# nRF51x22_qfaa.net
KiCad netlist of a schematic drawn in EAGLE
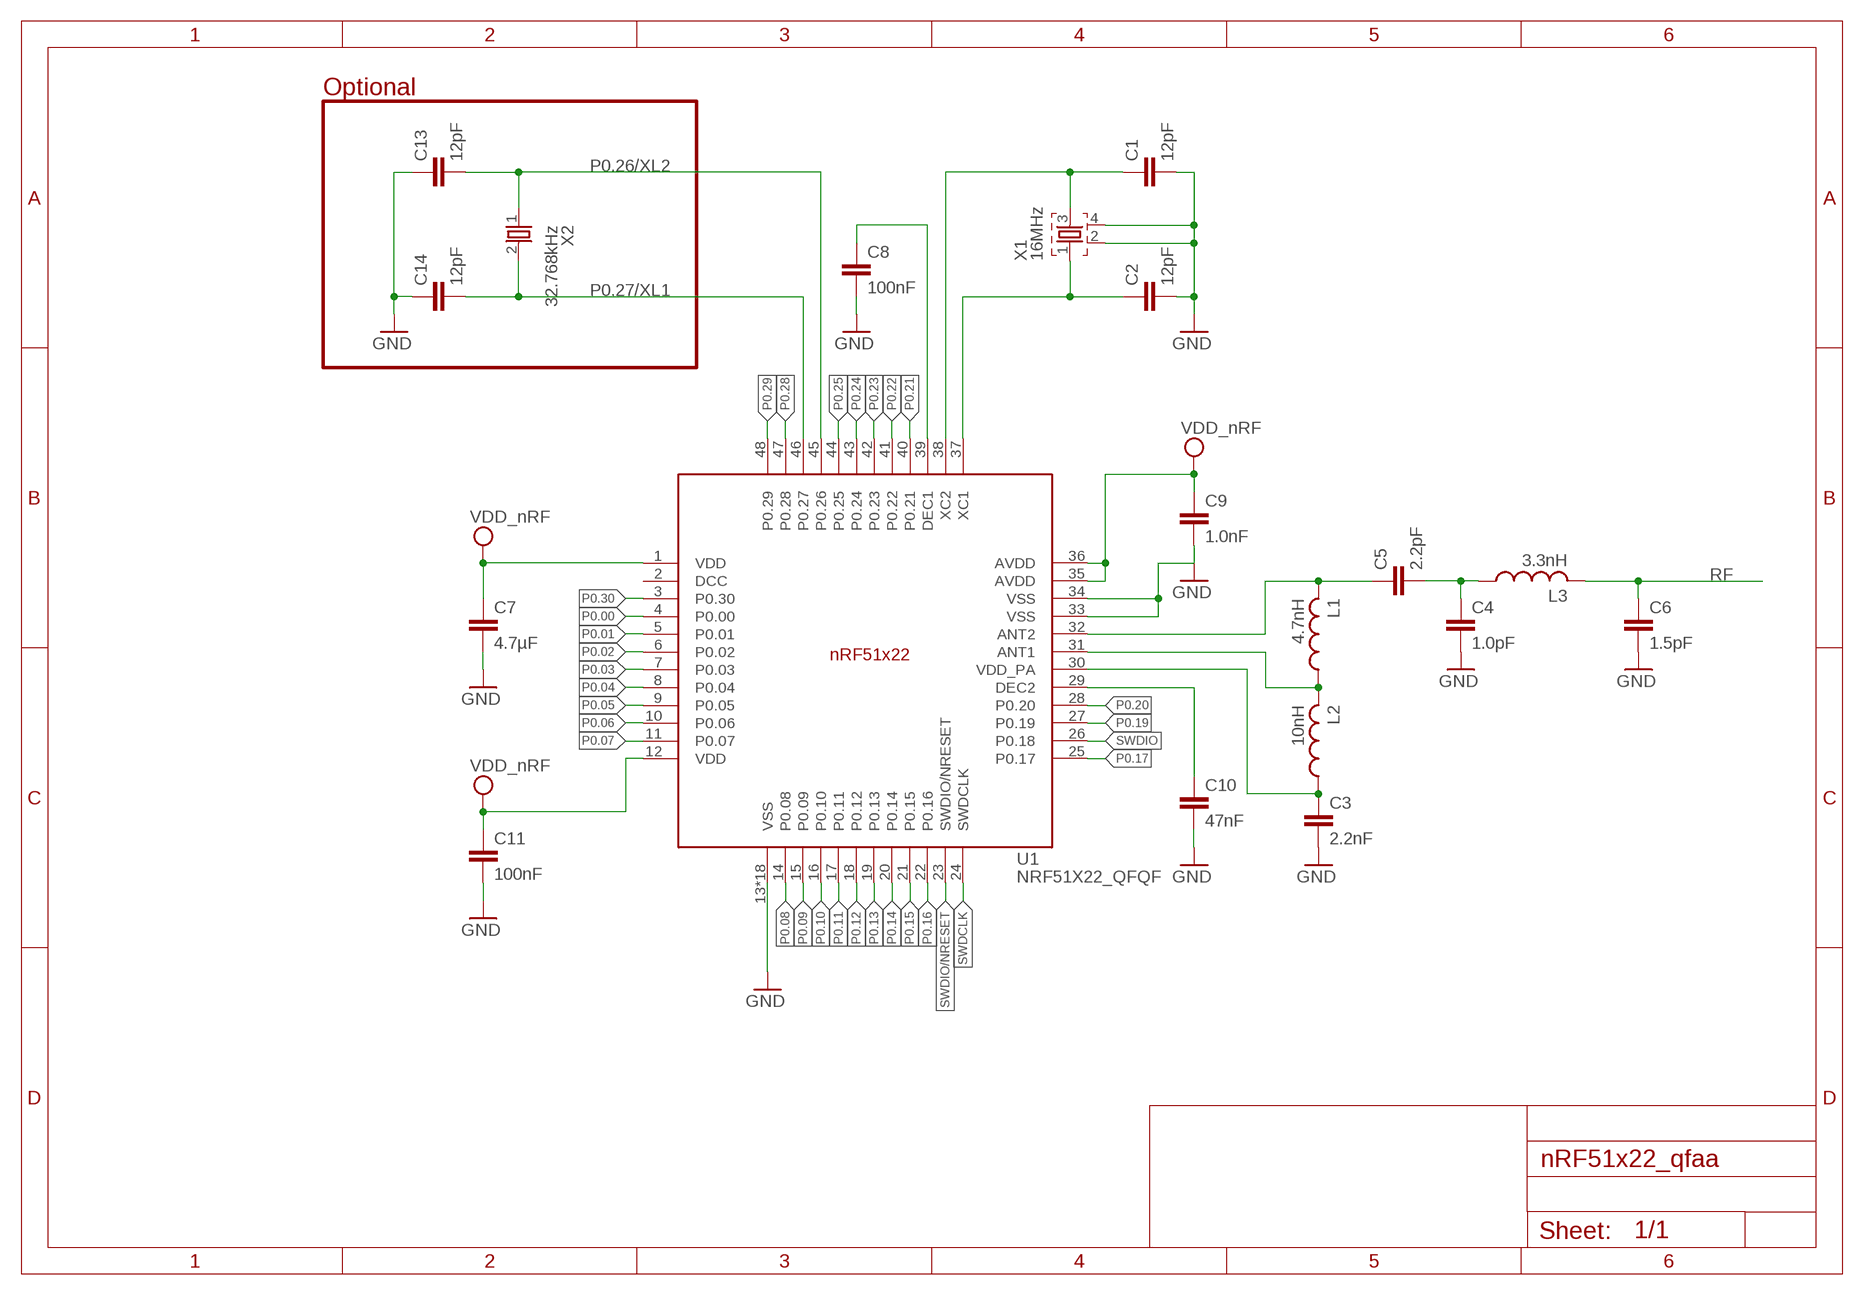
[diagram p0: schematic, sheet 1]

(export (version "E")
  (design (tool "Eeschema 10.0.6"))
  (components
    (comp (ref "C1")
      (value "12pF")
      (footprint "eagle-import:RESC0402_N")
      (libsource (lib "eagle-import") (part "CAPACITOR_0402_N"))
    )
    (comp (ref "C2")
      (value "12pF")
      (footprint "eagle-import:RESC0402_N")
      (libsource (lib "eagle-import") (part "CAPACITOR_0402_N"))
    )
    (comp (ref "C3")
      (value "2.2nF")
      (footprint "eagle-import:RESC0402_N")
      (libsource (lib "eagle-import") (part "CAPACITOR_0402_N"))
    )
    (comp (ref "C4")
      (value "1.0pF")
      (footprint "eagle-import:RESC0402_N")
      (libsource (lib "eagle-import") (part "CAPACITOR_0402_N"))
    )
    (comp (ref "C5")
      (value "2.2pF")
      (footprint "eagle-import:RESC0402_N")
      (libsource (lib "eagle-import") (part "CAPACITOR_0402_N"))
    )
    (comp (ref "C6")
      (value "1.5pF")
      (footprint "eagle-import:RESC0402_N")
      (libsource (lib "eagle-import") (part "CAPACITOR_0402_N"))
    )
    (comp (ref "C7")
      (value "4.7µF")
      (footprint "eagle-import:RESC0603_N")
      (libsource (lib "eagle-import") (part "CAPACITOR_0603_N"))
    )
    (comp (ref "C8")
      (value "100nF")
      (footprint "eagle-import:RESC0402_N")
      (libsource (lib "eagle-import") (part "CAPACITOR_0402_N"))
    )
    (comp (ref "C9")
      (value "1.0nF")
      (footprint "eagle-import:RESC0402_N")
      (libsource (lib "eagle-import") (part "CAPACITOR_0402_N"))
    )
    (comp (ref "C10")
      (value "47nF")
      (footprint "eagle-import:RESC0402_N")
      (libsource (lib "eagle-import") (part "CAPACITOR_0402_N"))
    )
    (comp (ref "C11")
      (value "100nF")
      (footprint "eagle-import:RESC0402_N")
      (libsource (lib "eagle-import") (part "CAPACITOR_0402_N"))
    )
    (comp (ref "C13")
      (value "12pF")
      (footprint "eagle-import:RESC0402_N")
      (libsource (lib "eagle-import") (part "CAPACITOR_0402_N"))
    )
    (comp (ref "C14")
      (value "12pF")
      (footprint "eagle-import:RESC0402_N")
      (libsource (lib "eagle-import") (part "CAPACITOR_0402_N"))
    )
    (comp (ref "L1")
      (value "4.7nH")
      (footprint "eagle-import:RESC0402_N")
      (libsource (lib "eagle-import") (part "INDUCTOR_0402_N"))
    )
    (comp (ref "L2")
      (value "10nH")
      (footprint "eagle-import:RESC0402_N")
      (libsource (lib "eagle-import") (part "INDUCTOR_0402_N"))
    )
    (comp (ref "L3")
      (value "3.3nH")
      (footprint "eagle-import:RESC0402_N")
      (libsource (lib "eagle-import") (part "INDUCTOR_0402_N"))
    )
    (comp (ref "U1")
      (value "NRF51X22_QFQF")
      (footprint "eagle-import:QFN40P600X600X90-48_N")
      (libsource (lib "eagle-import") (part "NRF51X22_QFQF"))
    )
    (comp (ref "X1")
      (value "16MHz")
      (footprint "eagle-import:BT-XTAL_2016_N")
      (libsource (lib "eagle-import") (part "XTAL_32MHZ"))
    )
    (comp (ref "X2")
      (value "32.768kHz")
      (footprint "eagle-import:XTAL_3215_N")
      (libsource (lib "eagle-import") (part "XTAL_32KHZ"))
    )
  )
  (nets
    (net (code "1") (name "/DCC") (class "Default")
      (node (ref "U1") (pin "2") (pinfunction "DCC_2") (pintype "power_in"))
    )
    (net (code "2") (name "/P0.26{slash}XL2") (class "Default")
      (node (ref "C13") (pin "2") (pinfunction "2_2") (pintype "passive"))
      (node (ref "U1") (pin "45") (pinfunction "P0.26_45") (pintype "bidirectional"))
      (node (ref "X2") (pin "1") (pinfunction "1_1") (pintype "passive"))
    )
    (net (code "3") (name "/P0.27{slash}XL1") (class "Default")
      (node (ref "C14") (pin "2") (pinfunction "2_2") (pintype "passive"))
      (node (ref "U1") (pin "46") (pinfunction "P0.27_46") (pintype "bidirectional"))
      (node (ref "X2") (pin "2") (pinfunction "2_2") (pintype "passive"))
    )
    (net (code "4") (name "/RF") (class "Default")
      (node (ref "C6") (pin "1") (pinfunction "1_1") (pintype "passive"))
      (node (ref "L3") (pin "2") (pinfunction "2_2") (pintype "passive"))
    )
    (net (code "5") (name "GND") (class "Default")
      (node (ref "C1") (pin "2") (pinfunction "2_2") (pintype "passive"))
      (node (ref "C10") (pin "2") (pinfunction "2_2") (pintype "passive"))
      (node (ref "C11") (pin "2") (pinfunction "2_2") (pintype "passive"))
      (node (ref "C13") (pin "1") (pinfunction "1_1") (pintype "passive"))
      (node (ref "C14") (pin "1") (pinfunction "1_1") (pintype "passive"))
      (node (ref "C2") (pin "2") (pinfunction "2_2") (pintype "passive"))
      (node (ref "C3") (pin "2") (pinfunction "2_2") (pintype "passive"))
      (node (ref "C4") (pin "2") (pinfunction "2_2") (pintype "passive"))
      (node (ref "C6") (pin "2") (pinfunction "2_2") (pintype "passive"))
      (node (ref "C7") (pin "2") (pinfunction "2_2") (pintype "passive"))
      (node (ref "C8") (pin "2") (pinfunction "2_2") (pintype "passive"))
      (node (ref "C9") (pin "2") (pinfunction "2_2") (pintype "passive"))
      (node (ref "U1") (pin "13") (pinfunction "VSS_13") (pintype "power_in"))
      (node (ref "U1") (pin "33") (pinfunction "VSS_33") (pintype "power_in"))
      (node (ref "U1") (pin "34") (pinfunction "VSS_34") (pintype "power_in"))
      (node (ref "U1") (pin "PAD") (pinfunction "VSS_PAD") (pintype "power_in"))
      (node (ref "U1") (pin "PAD@VIA01") (pinfunction "VSS_PAD@VIA01") (pintype "power_in"))
      (node (ref "U1") (pin "PAD@VIA02") (pinfunction "VSS_PAD@VIA02") (pintype "power_in"))
      (node (ref "U1") (pin "PAD@VIA03") (pinfunction "VSS_PAD@VIA03") (pintype "power_in"))
      (node (ref "U1") (pin "PAD@VIA04") (pinfunction "VSS_PAD@VIA04") (pintype "power_in"))
      (node (ref "U1") (pin "PAD@VIA05") (pinfunction "VSS_PAD@VIA05") (pintype "power_in"))
      (node (ref "U1") (pin "PAD@VIA06") (pinfunction "VSS_PAD@VIA06") (pintype "power_in"))
      (node (ref "U1") (pin "PAD@VIA07") (pinfunction "VSS_PAD@VIA07") (pintype "power_in"))
      (node (ref "U1") (pin "PAD@VIA08") (pinfunction "VSS_PAD@VIA08") (pintype "power_in"))
      (node (ref "U1") (pin "PAD@VIA09") (pinfunction "VSS_PAD@VIA09") (pintype "power_in"))
      (node (ref "U1") (pin "PAD@VIA10") (pinfunction "VSS_PAD@VIA10") (pintype "power_in"))
      (node (ref "U1") (pin "PAD@VIA11") (pinfunction "VSS_PAD@VIA11") (pintype "power_in"))
      (node (ref "U1") (pin "PAD@VIA12") (pinfunction "VSS_PAD@VIA12") (pintype "power_in"))
      (node (ref "U1") (pin "PAD@VIA13") (pinfunction "VSS_PAD@VIA13") (pintype "power_in"))
      (node (ref "U1") (pin "PAD@VIA14") (pinfunction "VSS_PAD@VIA14") (pintype "power_in"))
      (node (ref "U1") (pin "PAD@VIA15") (pinfunction "VSS_PAD@VIA15") (pintype "power_in"))
      (node (ref "U1") (pin "PAD@VIA16") (pinfunction "VSS_PAD@VIA16") (pintype "power_in"))
      (node (ref "X1") (pin "2") (pinfunction "2_2") (pintype "passive"))
      (node (ref "X1") (pin "4") (pinfunction "4_4") (pintype "passive"))
    )
    (net (code "6") (name "Net-(C4-Pad1)") (class "Default")
      (node (ref "C4") (pin "1") (pinfunction "1_1") (pintype "passive"))
      (node (ref "C5") (pin "2") (pinfunction "2_2") (pintype "passive"))
      (node (ref "L3") (pin "1") (pinfunction "1_1") (pintype "passive"))
    )
    (net (code "7") (name "Net-(U1-ANT1)") (class "Default")
      (node (ref "L1") (pin "1") (pinfunction "1_1") (pintype "passive"))
      (node (ref "L2") (pin "2") (pinfunction "2_2") (pintype "passive"))
      (node (ref "U1") (pin "31") (pinfunction "ANT1_31") (pintype "bidirectional"))
    )
    (net (code "8") (name "Net-(U1-ANT2)") (class "Default")
      (node (ref "C5") (pin "1") (pinfunction "1_1") (pintype "passive"))
      (node (ref "L1") (pin "2") (pinfunction "2_2") (pintype "passive"))
      (node (ref "U1") (pin "32") (pinfunction "ANT2_32") (pintype "bidirectional"))
    )
    (net (code "9") (name "Net-(U1-DEC1)") (class "Default")
      (node (ref "C8") (pin "1") (pinfunction "1_1") (pintype "passive"))
      (node (ref "U1") (pin "39") (pinfunction "DEC1_39") (pintype "power_in"))
    )
    (net (code "10") (name "Net-(U1-DEC2)") (class "Default")
      (node (ref "C10") (pin "1") (pinfunction "1_1") (pintype "passive"))
      (node (ref "U1") (pin "29") (pinfunction "DEC2_29") (pintype "power_in"))
    )
    (net (code "11") (name "Net-(U1-VDD_PA)") (class "Default")
      (node (ref "C3") (pin "1") (pinfunction "1_1") (pintype "passive"))
      (node (ref "L2") (pin "1") (pinfunction "1_1") (pintype "passive"))
      (node (ref "U1") (pin "30") (pinfunction "VDD_PA_30") (pintype "power_in"))
    )
    (net (code "12") (name "Net-(U1-XC1)") (class "Default")
      (node (ref "C2") (pin "1") (pinfunction "1_1") (pintype "passive"))
      (node (ref "U1") (pin "37") (pinfunction "XC1_37") (pintype "bidirectional"))
      (node (ref "X1") (pin "1") (pinfunction "1_1") (pintype "passive"))
    )
    (net (code "13") (name "Net-(U1-XC2)") (class "Default")
      (node (ref "C1") (pin "1") (pinfunction "1_1") (pintype "passive"))
      (node (ref "U1") (pin "38") (pinfunction "XC2_38") (pintype "bidirectional"))
      (node (ref "X1") (pin "3") (pinfunction "3_3") (pintype "passive"))
    )
    (net (code "14") (name "P0.00") (class "Default")
      (node (ref "U1") (pin "4") (pinfunction "P0.00_4") (pintype "bidirectional"))
    )
    (net (code "15") (name "P0.01") (class "Default")
      (node (ref "U1") (pin "5") (pinfunction "P0.01_5") (pintype "bidirectional"))
    )
    (net (code "16") (name "P0.02") (class "Default")
      (node (ref "U1") (pin "6") (pinfunction "P0.02_6") (pintype "bidirectional"))
    )
    (net (code "17") (name "P0.03") (class "Default")
      (node (ref "U1") (pin "7") (pinfunction "P0.03_7") (pintype "bidirectional"))
    )
    (net (code "18") (name "P0.04") (class "Default")
      (node (ref "U1") (pin "8") (pinfunction "P0.04_8") (pintype "bidirectional"))
    )
    (net (code "19") (name "P0.05") (class "Default")
      (node (ref "U1") (pin "9") (pinfunction "P0.05_9") (pintype "bidirectional"))
    )
    (net (code "20") (name "P0.06") (class "Default")
      (node (ref "U1") (pin "10") (pinfunction "P0.06_10") (pintype "bidirectional"))
    )
    (net (code "21") (name "P0.07") (class "Default")
      (node (ref "U1") (pin "11") (pinfunction "P0.07_11") (pintype "bidirectional"))
    )
    (net (code "22") (name "P0.08") (class "Default")
      (node (ref "U1") (pin "14") (pinfunction "P0.08_14") (pintype "bidirectional"))
    )
    (net (code "23") (name "P0.09") (class "Default")
      (node (ref "U1") (pin "15") (pinfunction "P0.09_15") (pintype "bidirectional"))
    )
    (net (code "24") (name "P0.10") (class "Default")
      (node (ref "U1") (pin "16") (pinfunction "P0.10_16") (pintype "bidirectional"))
    )
    (net (code "25") (name "P0.11") (class "Default")
      (node (ref "U1") (pin "17") (pinfunction "P0.11_17") (pintype "bidirectional"))
    )
    (net (code "26") (name "P0.12") (class "Default")
      (node (ref "U1") (pin "18") (pinfunction "P0.12_18") (pintype "bidirectional"))
    )
    (net (code "27") (name "P0.13") (class "Default")
      (node (ref "U1") (pin "19") (pinfunction "P0.13_19") (pintype "bidirectional"))
    )
    (net (code "28") (name "P0.14") (class "Default")
      (node (ref "U1") (pin "20") (pinfunction "P0.14_20") (pintype "bidirectional"))
    )
    (net (code "29") (name "P0.15") (class "Default")
      (node (ref "U1") (pin "21") (pinfunction "P0.15_21") (pintype "bidirectional"))
    )
    (net (code "30") (name "P0.16") (class "Default")
      (node (ref "U1") (pin "22") (pinfunction "P0.16_22") (pintype "bidirectional"))
    )
    (net (code "31") (name "P0.17") (class "Default")
      (node (ref "U1") (pin "25") (pinfunction "P0.17_25") (pintype "bidirectional"))
    )
    (net (code "32") (name "P0.19") (class "Default")
      (node (ref "U1") (pin "27") (pinfunction "P0.19_27") (pintype "bidirectional"))
    )
    (net (code "33") (name "P0.20") (class "Default")
      (node (ref "U1") (pin "28") (pinfunction "P0.20_28") (pintype "bidirectional"))
    )
    (net (code "34") (name "P0.21") (class "Default")
      (node (ref "U1") (pin "40") (pinfunction "P0.21_40") (pintype "bidirectional"))
    )
    (net (code "35") (name "P0.22") (class "Default")
      (node (ref "U1") (pin "41") (pinfunction "P0.22_41") (pintype "bidirectional"))
    )
    (net (code "36") (name "P0.23") (class "Default")
      (node (ref "U1") (pin "42") (pinfunction "P0.23_42") (pintype "bidirectional"))
    )
    (net (code "37") (name "P0.24") (class "Default")
      (node (ref "U1") (pin "43") (pinfunction "P0.24_43") (pintype "bidirectional"))
    )
    (net (code "38") (name "P0.25") (class "Default")
      (node (ref "U1") (pin "44") (pinfunction "P0.25_44") (pintype "bidirectional"))
    )
    (net (code "39") (name "P0.28") (class "Default")
      (node (ref "U1") (pin "47") (pinfunction "P0.28_47") (pintype "bidirectional"))
    )
    (net (code "40") (name "P0.29") (class "Default")
      (node (ref "U1") (pin "48") (pinfunction "P0.29_48") (pintype "bidirectional"))
    )
    (net (code "41") (name "P0.30") (class "Default")
      (node (ref "U1") (pin "3") (pinfunction "P0.30_3") (pintype "bidirectional"))
    )
    (net (code "42") (name "SWDCLK") (class "Default")
      (node (ref "U1") (pin "24") (pinfunction "SWDCLK_24") (pintype "input"))
    )
    (net (code "43") (name "SWDIO") (class "Default")
      (node (ref "U1") (pin "26") (pinfunction "P0.18_26") (pintype "bidirectional"))
    )
    (net (code "44") (name "SWDIO{slash}NRESET") (class "Default")
      (node (ref "U1") (pin "23") (pinfunction "SWDIO/NRESET_23") (pintype "bidirectional"))
    )
    (net (code "45") (name "VDD_nRF") (class "Default")
      (node (ref "C11") (pin "1") (pinfunction "1_1") (pintype "passive"))
      (node (ref "C7") (pin "1") (pinfunction "1_1") (pintype "passive"))
      (node (ref "C9") (pin "1") (pinfunction "1_1") (pintype "passive"))
      (node (ref "U1") (pin "1") (pinfunction "VDD_1") (pintype "power_in"))
      (node (ref "U1") (pin "12") (pinfunction "VDD_12") (pintype "power_in"))
      (node (ref "U1") (pin "35") (pinfunction "AVDD_35") (pintype "power_in"))
      (node (ref "U1") (pin "36") (pinfunction "AVDD_36") (pintype "power_in"))
    )
  )
)
